# Microcontroller.net
KiCad netlist of a schematic drawn in Altium Designer
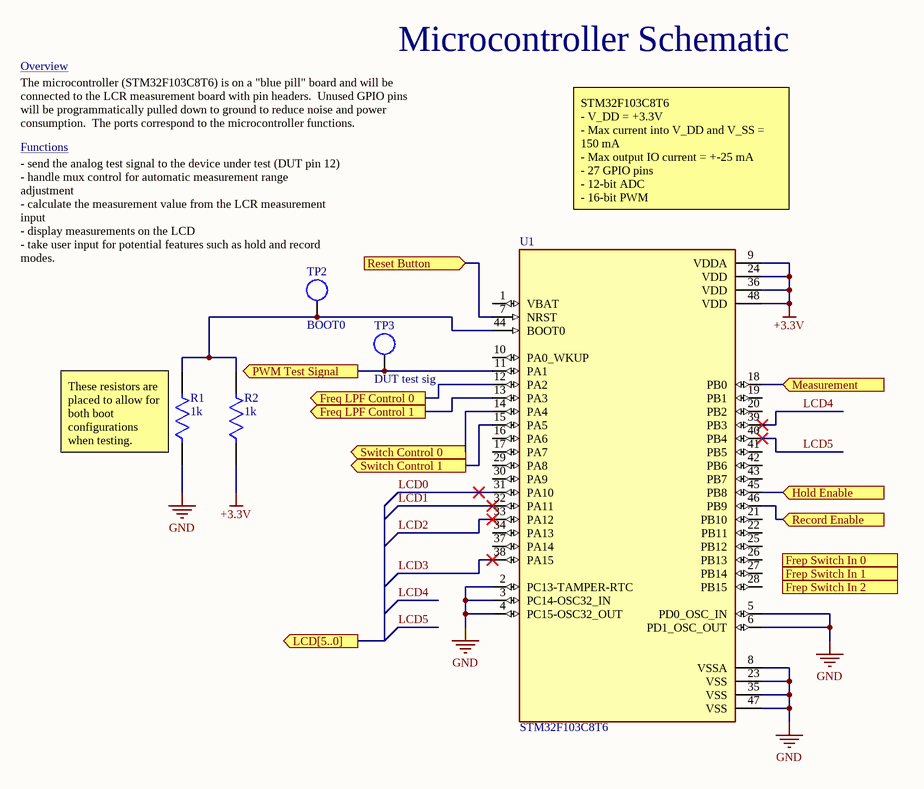
[diagram p0: Microcontroller.SchDoc]

(export (version "E")
  (design (tool "Eeschema 10.0.6"))
  (components
    (comp (ref "R1")
      (value "1k")
      (footprint "FP-RNCP0805-MFG")
      (description "1kΩ ±1% 0.25W 0805 High Power Anti-Sulfur Thin Film Chip Resistor")
      (fields (field (name "TOLERANCE") "1%"))
      (libsource (lib "Altium Content Vault") (part "1029c3af85768c4190bb7ad29bc67b5"))
    )
    (comp (ref "R2")
      (value "1k")
      (footprint "FP-RNCP0805-MFG")
      (description "1kΩ ±1% 0.25W 0805 High Power Anti-Sulfur Thin Film Chip Resistor")
      (fields (field (name "TOLERANCE") "1%"))
      (libsource (lib "Altium Content Vault") (part "1029c3af85768c4190bb7ad29bc67b5"))
    )
    (comp (ref "TP2")
      (value "BOOT0")
      (footprint "PCBComponent_1")
      (libsource (lib "test-point") (part "Component_1"))
    )
    (comp (ref "TP3")
      (value "DUT test sig")
      (footprint "PCBComponent_1")
      (libsource (lib "test-point") (part "Component_1"))
    )
    (comp (ref "U1")
      (value "STM32F103C8T6")
      (footprint "QFP50P900X900X160-48N")
      (description "ARMÂ® CortexÂ®-M3 STM32F1 Microcontroller IC 32-Bit 72MHz 64KB _64K x 8_ FLASH")
      (fields (field (name "MF") "STMicroelectronics"))
      (libsource (lib "STM32F103C8T6") (part "STM32F103C8T6"))
    )
  )
  (nets
    (net (code "1") (name "+3.3V") (class "Default")
      (node (ref "R2") (pin "1") (pinfunction "1_1") (pintype "passive"))
      (node (ref "U1") (pin "24") (pinfunction "VDD_24") (pintype "power_in"))
      (node (ref "U1") (pin "36") (pinfunction "VDD_36") (pintype "power_in"))
      (node (ref "U1") (pin "48") (pinfunction "VDD_48") (pintype "power_in"))
      (node (ref "U1") (pin "9") (pinfunction "VDDA_9") (pintype "power_in"))
    )
    (net (code "5") (name "/Freq LPF Control 0") (class "Default")
      (node (ref "U1") (pin "12") (pinfunction "PA2_12") (pintype "bidirectional"))
    )
    (net (code "6") (name "/Freq LPF Control 1") (class "Default")
      (node (ref "U1") (pin "13") (pinfunction "PA3_13") (pintype "bidirectional"))
    )
    (net (code "7") (name "/Hold Enable") (class "Default")
      (node (ref "U1") (pin "45") (pinfunction "PB8_45") (pintype "bidirectional"))
    )
    (net (code "8") (name "/LCD0") (class "Default")
      (node (ref "U1") (pin "31") (pinfunction "PA10_31") (pintype "bidirectional"))
    )
    (net (code "9") (name "/LCD1") (class "Default")
      (node (ref "U1") (pin "32") (pinfunction "PA11_32") (pintype "bidirectional+no_connect"))
    )
    (net (code "10") (name "/LCD2") (class "Default")
      (node (ref "U1") (pin "33") (pinfunction "PA12_33") (pintype "bidirectional+no_connect"))
    )
    (net (code "11") (name "/LCD3") (class "Default")
      (node (ref "U1") (pin "38") (pinfunction "PA15_38") (pintype "bidirectional+no_connect"))
    )
    (net (code "12") (name "/LCD4") (class "Default")
      (node (ref "U1") (pin "39") (pinfunction "PB3_39") (pintype "bidirectional+no_connect"))
    )
    (net (code "13") (name "/LCD5") (class "Default")
      (node (ref "U1") (pin "40") (pinfunction "PB4_40") (pintype "bidirectional+no_connect"))
    )
    (net (code "15") (name "/Measurement") (class "Default")
      (node (ref "U1") (pin "18") (pinfunction "PB0_18") (pintype "bidirectional"))
    )
    (net (code "16") (name "/PWM Test Signal") (class "Default")
      (node (ref "TP3") (pin "TP") (pinfunction "TP_TP") (pintype "passive"))
      (node (ref "U1") (pin "11") (pinfunction "PA1_11") (pintype "bidirectional"))
    )
    (net (code "17") (name "/Record Enable") (class "Default")
      (node (ref "U1") (pin "46") (pinfunction "PB9_46") (pintype "bidirectional"))
    )
    (net (code "18") (name "/Reset Button") (class "Default")
      (node (ref "U1") (pin "7") (pinfunction "NRST_7") (pintype "input"))
    )
    (net (code "19") (name "/Switch Control 0") (class "Default")
      (node (ref "U1") (pin "14") (pinfunction "PA4_14") (pintype "bidirectional"))
    )
    (net (code "20") (name "/Switch Control 1") (class "Default")
      (node (ref "U1") (pin "15") (pinfunction "PA5_15") (pintype "bidirectional"))
    )
    (net (code "21") (name "GND") (class "Default")
      (node (ref "R1") (pin "1") (pinfunction "1_1") (pintype "passive"))
      (node (ref "U1") (pin "2") (pinfunction "PC13-TAMPER-RTC_2") (pintype "bidirectional"))
      (node (ref "U1") (pin "23") (pinfunction "VSS_23") (pintype "power_in"))
      (node (ref "U1") (pin "3") (pinfunction "PC14-OSC32_IN_3") (pintype "bidirectional"))
      (node (ref "U1") (pin "35") (pinfunction "VSS_35") (pintype "power_in"))
      (node (ref "U1") (pin "4") (pinfunction "PC15-OSC32_OUT_4") (pintype "bidirectional"))
      (node (ref "U1") (pin "47") (pinfunction "VSS_47") (pintype "power_in"))
      (node (ref "U1") (pin "5") (pinfunction "PD0_OSC_IN_5") (pintype "bidirectional"))
      (node (ref "U1") (pin "6") (pinfunction "PD1_OSC_OUT_6") (pintype "bidirectional"))
      (node (ref "U1") (pin "8") (pinfunction "VSSA_8") (pintype "power_in"))
    )
    (net (code "22") (name "Net-(U1-BOOT0)") (class "Default")
      (node (ref "R1") (pin "2") (pinfunction "2_2") (pintype "passive"))
      (node (ref "R2") (pin "2") (pinfunction "2_2") (pintype "passive"))
      (node (ref "TP2") (pin "TP") (pinfunction "TP_TP") (pintype "passive"))
      (node (ref "U1") (pin "44") (pinfunction "BOOT0_44") (pintype "input"))
    )
    (net (code "23") (name "unconnected-(U1-PA0_WKUP-Pad10)") (class "Default")
      (node (ref "U1") (pin "10") (pinfunction "PA0_WKUP_10") (pintype "bidirectional"))
    )
    (net (code "24") (name "unconnected-(U1-PA6-Pad16)") (class "Default")
      (node (ref "U1") (pin "16") (pinfunction "PA6_16") (pintype "bidirectional"))
    )
    (net (code "25") (name "unconnected-(U1-PA7-Pad17)") (class "Default")
      (node (ref "U1") (pin "17") (pinfunction "PA7_17") (pintype "bidirectional"))
    )
    (net (code "26") (name "unconnected-(U1-PA8-Pad29)") (class "Default")
      (node (ref "U1") (pin "29") (pinfunction "PA8_29") (pintype "bidirectional"))
    )
    (net (code "27") (name "unconnected-(U1-PA9-Pad30)") (class "Default")
      (node (ref "U1") (pin "30") (pinfunction "PA9_30") (pintype "bidirectional"))
    )
    (net (code "28") (name "unconnected-(U1-PA13-Pad34)") (class "Default")
      (node (ref "U1") (pin "34") (pinfunction "PA13_34") (pintype "bidirectional"))
    )
    (net (code "29") (name "unconnected-(U1-PA14-Pad37)") (class "Default")
      (node (ref "U1") (pin "37") (pinfunction "PA14_37") (pintype "bidirectional"))
    )
    (net (code "30") (name "unconnected-(U1-PB1-Pad19)") (class "Default")
      (node (ref "U1") (pin "19") (pinfunction "PB1_19") (pintype "bidirectional"))
    )
    (net (code "31") (name "unconnected-(U1-PB2-Pad20)") (class "Default")
      (node (ref "U1") (pin "20") (pinfunction "PB2_20") (pintype "bidirectional"))
    )
    (net (code "32") (name "unconnected-(U1-PB5-Pad41)") (class "Default")
      (node (ref "U1") (pin "41") (pinfunction "PB5_41") (pintype "bidirectional"))
    )
    (net (code "33") (name "unconnected-(U1-PB6-Pad42)") (class "Default")
      (node (ref "U1") (pin "42") (pinfunction "PB6_42") (pintype "bidirectional"))
    )
    (net (code "34") (name "unconnected-(U1-PB7-Pad43)") (class "Default")
      (node (ref "U1") (pin "43") (pinfunction "PB7_43") (pintype "bidirectional"))
    )
    (net (code "35") (name "unconnected-(U1-PB10-Pad21)") (class "Default")
      (node (ref "U1") (pin "21") (pinfunction "PB10_21") (pintype "bidirectional"))
    )
    (net (code "36") (name "unconnected-(U1-PB11-Pad22)") (class "Default")
      (node (ref "U1") (pin "22") (pinfunction "PB11_22") (pintype "bidirectional"))
    )
    (net (code "37") (name "unconnected-(U1-PB12-Pad25)") (class "Default")
      (node (ref "U1") (pin "25") (pinfunction "PB12_25") (pintype "bidirectional"))
    )
    (net (code "38") (name "unconnected-(U1-PB13-Pad26)") (class "Default")
      (node (ref "U1") (pin "26") (pinfunction "PB13_26") (pintype "bidirectional"))
    )
    (net (code "39") (name "unconnected-(U1-PB14-Pad27)") (class "Default")
      (node (ref "U1") (pin "27") (pinfunction "PB14_27") (pintype "bidirectional"))
    )
    (net (code "40") (name "unconnected-(U1-PB15-Pad28)") (class "Default")
      (node (ref "U1") (pin "28") (pinfunction "PB15_28") (pintype "bidirectional"))
    )
    (net (code "41") (name "unconnected-(U1-VBAT-Pad1)") (class "Default")
      (node (ref "U1") (pin "1") (pinfunction "VBAT_1") (pintype "bidirectional"))
    )
  )
)
